# Waveform_Generator_Design.net
KiCad netlist of a schematic drawn in Altium Designer
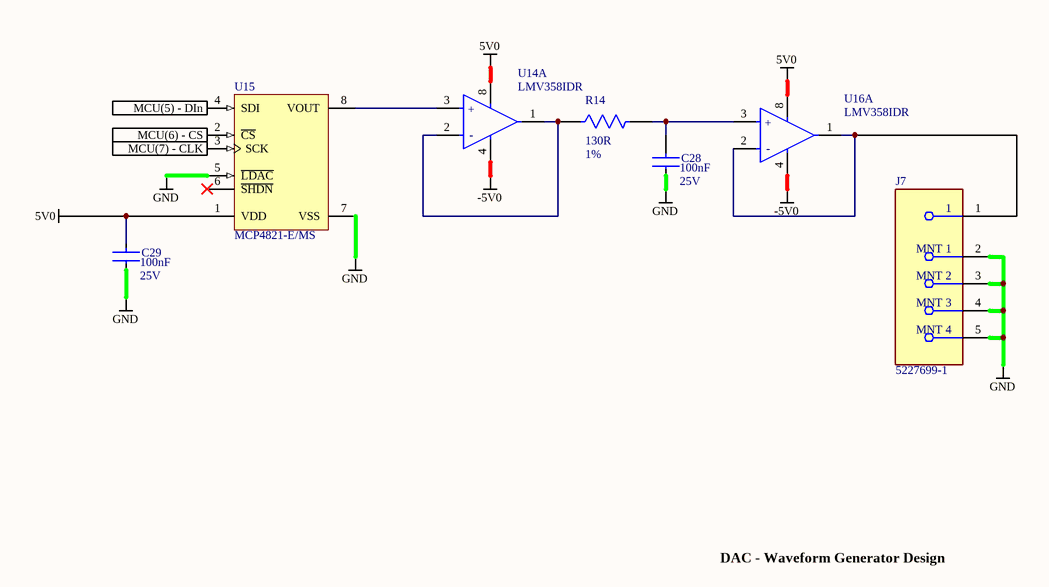
[diagram p0: Waveform Generator Design.SchDoc]

(export (version "E")
  (design (tool "Eeschema 10.0.6"))
  (components
    (comp (ref "C28")
      (value "0.1 uF")
      (footprint "FP-CL278-IPC_C")
      (description "Cap Ceramic 100nF 25V X5R ±10% SMD 0402 +85°C Paper T/R")
      (fields
        (field (name "VOLTAGE") "25V")
        (field (name "VOLTAGE RATING") "25V")
        (field (name "TOLERANCE") "10%")
        (field (name "CAPACITANCE") "100nF")
      )
      (libsource (lib "Altium Content Vault") (part "b4654b650e69147ec39a6b967a45e02"))
    )
    (comp (ref "C29")
      (value "0.1 uF")
      (footprint "FP-CL278-IPC_C")
      (description "Cap Ceramic 100nF 25V X5R ±10% SMD 0402 +85°C Paper T/R")
      (fields
        (field (name "VOLTAGE") "25V")
        (field (name "VOLTAGE RATING") "25V")
        (field (name "TOLERANCE") "10%")
        (field (name "CAPACITANCE") "100nF")
      )
      (libsource (lib "Altium Content Vault") (part "b4654b650e69147ec39a6b967a45e02"))
    )
    (comp (ref "J7")
      (value "5227699-1")
      (footprint "FP-5227699-1-MFG")
      (description "CONN BNC JACK STR 50 OHM PCB")
      (libsource (lib "Altium Content Vault") (part "c65b8a639cdaef1819ea20b5466f8fa"))
    )
    (comp (ref "R14")
      (value "130 Ohm")
      (footprint "FP-CRCW2512-e3-IPC_C")
      (description "RES Thick Film, 130Ω, 1%, 1W, 100ppm/°C, 2512")
      (fields (field (name "TOLERANCE") "1%") (field (name "RESISTANCE") "130R"))
      (libsource (lib "Altium Content Vault") (part "1029c3af85768c4190bb7ad29bc67b5"))
    )
    (comp (ref "U14")
      (value "LMV358IDR")
      (footprint "FP-D0008A-MFG")
      (description "IC OPAMP GP 2 CIRCUIT 8SOIC")
      (libsource (lib "Altium Content Vault") (part "1f85fec4e6914445158f776dbf16c1d"))
    )
    (comp (ref "U15")
      (value "MCP4821-E/MS")
      (footprint "MSOP-MS8_N")
      (description "12-Bit DACs with Internal VREF and SPI Interface, 8-Pin MSOP, Extended Temperature")
      (libsource (lib "Altium Content Vault") (part "CON-DAC-MCP4821-8"))
    )
    (comp (ref "U16")
      (value "LMV358IDR")
      (footprint "FP-D0008A-MFG")
      (description "IC OPAMP GP 2 CIRCUIT 8SOIC")
      (libsource (lib "Altium Content Vault") (part "1f85fec4e6914445158f776dbf16c1d"))
    )
  )
  (nets
    (net (code "1") (name "-5V0") (class "Default")
      (node (ref "U14") (pin "4") (pinfunction "GND_4") (pintype "power_in"))
      (node (ref "U16") (pin "4") (pinfunction "GND_4") (pintype "power_in"))
    )
    (net (code "2") (name "/MCU(5) - DIn") (class "Default")
      (node (ref "U15") (pin "4") (pinfunction "SDI_4") (pintype "input"))
    )
    (net (code "3") (name "/MCU(6) - CS") (class "Default")
      (node (ref "U15") (pin "2") (pinfunction "~{CS}_2") (pintype "input"))
    )
    (net (code "4") (name "/MCU(7) - CLK") (class "Default")
      (node (ref "U15") (pin "3") (pinfunction "SCK_3") (pintype "input"))
    )
    (net (code "5") (name "5V0") (class "Default")
      (node (ref "C29") (pin "1") (pinfunction "1_1") (pintype "passive"))
      (node (ref "U14") (pin "8") (pinfunction "VCC+_8") (pintype "power_in"))
      (node (ref "U15") (pin "1") (pinfunction "VDD_1") (pintype "power_in"))
      (node (ref "U16") (pin "8") (pinfunction "VCC+_8") (pintype "power_in"))
    )
    (net (code "6") (name "GND") (class "Default")
      (node (ref "C28") (pin "2") (pinfunction "2_2") (pintype "passive"))
      (node (ref "C29") (pin "2") (pinfunction "2_2") (pintype "passive"))
      (node (ref "J7") (pin "2") (pinfunction "MNT_1_2") (pintype "passive"))
      (node (ref "J7") (pin "3") (pinfunction "MNT_2_3") (pintype "passive"))
      (node (ref "J7") (pin "4") (pinfunction "MNT_3_4") (pintype "passive"))
      (node (ref "J7") (pin "5") (pinfunction "MNT_4_5") (pintype "passive"))
      (node (ref "U15") (pin "5") (pinfunction "~{LDAC}_5") (pintype "input"))
      (node (ref "U15") (pin "7") (pinfunction "VSS_7") (pintype "power_in"))
    )
    (net (code "7") (name "Net-(U14A-1IN+)") (class "Default")
      (node (ref "U14") (pin "3") (pinfunction "1IN+_3") (pintype "passive"))
      (node (ref "U15") (pin "8") (pinfunction "VOUT_8") (pintype "passive"))
    )
    (net (code "8") (name "Net-(U14A-1IN-)") (class "Default")
      (node (ref "R14") (pin "1") (pinfunction "1_1") (pintype "passive"))
      (node (ref "U14") (pin "1") (pinfunction "OUT_1") (pintype "passive"))
      (node (ref "U14") (pin "2") (pinfunction "1IN-_2") (pintype "passive"))
    )
    (net (code "9") (name "Net-(U16A-1IN+)") (class "Default")
      (node (ref "C28") (pin "1") (pinfunction "1_1") (pintype "passive"))
      (node (ref "R14") (pin "2") (pinfunction "2_2") (pintype "passive"))
      (node (ref "U16") (pin "3") (pinfunction "1IN+_3") (pintype "passive"))
    )
    (net (code "10") (name "Net-(U16A-1IN-)") (class "Default")
      (node (ref "J7") (pin "1") (pinfunction "1_1") (pintype "passive"))
      (node (ref "U16") (pin "1") (pinfunction "OUT_1") (pintype "passive"))
      (node (ref "U16") (pin "2") (pinfunction "1IN-_2") (pintype "passive"))
    )
    (net (code "11") (name "unconnected-(U15-~{SHDN}-Pad6)") (class "Default")
      (node (ref "U15") (pin "6") (pinfunction "~{SHDN}_6") (pintype "passive+no_connect"))
    )
  )
)
